# Keypad_Controller.net
KiCad netlist of a schematic drawn in Altium Designer
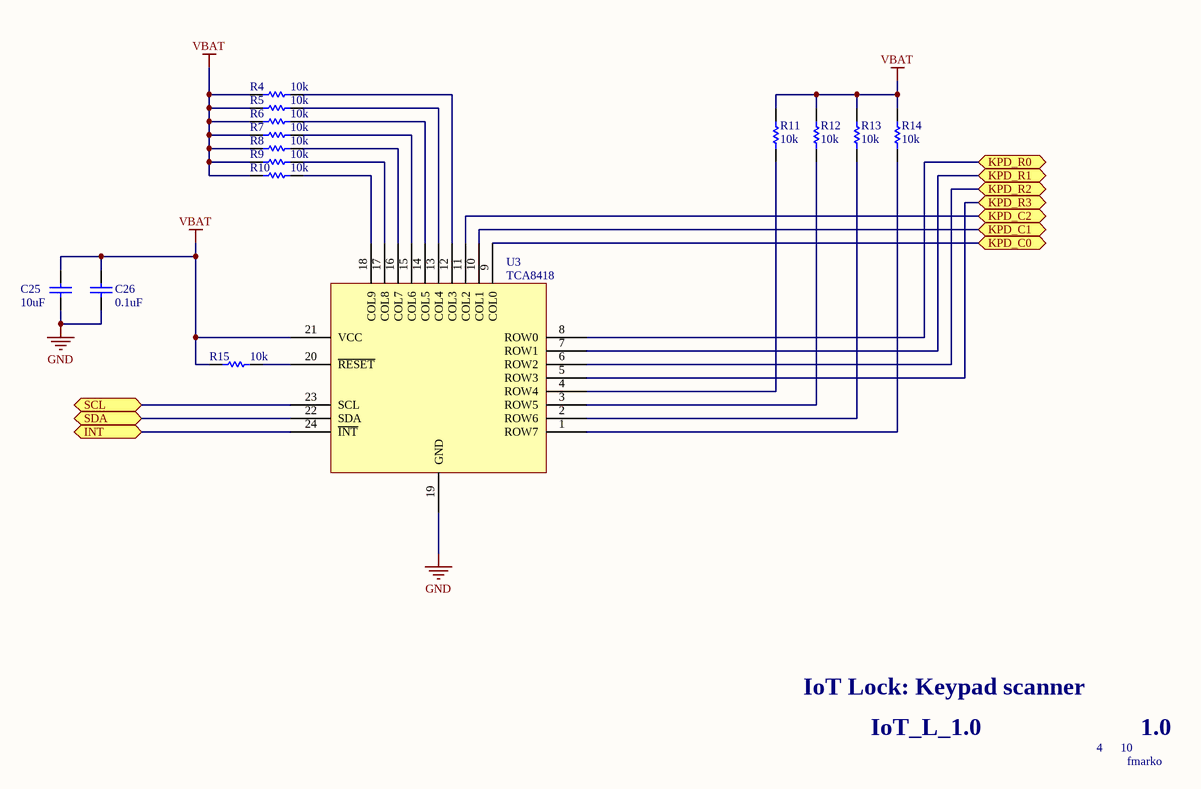
[diagram p0: Keypad Controller.SchDoc]

(export (version "E")
  (design (tool "Eeschema 10.0.6"))
  (components
    (comp (ref "C25")
      (value "10uF")
      (footprint "1608[0603]")
      (description "Capacitor")
      (fields (field (name "Comment") "GRM1555C1HR50BA01D") (field (name "PUBLISHER") "Altium Limited"))
      (libsource (lib "Miscellaneous Devices") (part "Cap"))
    )
    (comp (ref "C26")
      (value "0.1uF")
      (footprint "0402")
      (description "Capacitor")
      (fields (field (name "Comment") "GRM1555C1HR50BA01D") (field (name "PUBLISHER") "Altium Limited"))
      (libsource (lib "Miscellaneous Devices") (part "Cap"))
    )
    (comp (ref "R4")
      (value "10k")
      (footprint "0402")
      (description "Semiconductor Resistor")
      (fields (field (name "Comment") "Res Semi") (field (name "PUBLISHER") "Altium Limited"))
      (libsource (lib "Miscellaneous Devices") (part "Res Semi"))
    )
    (comp (ref "R5")
      (value "10k")
      (footprint "0402")
      (description "Semiconductor Resistor")
      (fields (field (name "Comment") "Res Semi") (field (name "PUBLISHER") "Altium Limited"))
      (libsource (lib "Miscellaneous Devices") (part "Res Semi"))
    )
    (comp (ref "R6")
      (value "10k")
      (footprint "0402")
      (description "Semiconductor Resistor")
      (fields (field (name "Comment") "Res Semi") (field (name "PUBLISHER") "Altium Limited"))
      (libsource (lib "Miscellaneous Devices") (part "Res Semi"))
    )
    (comp (ref "R7")
      (value "10k")
      (footprint "0402")
      (description "Semiconductor Resistor")
      (fields (field (name "Comment") "Res Semi") (field (name "PUBLISHER") "Altium Limited"))
      (libsource (lib "Miscellaneous Devices") (part "Res Semi"))
    )
    (comp (ref "R8")
      (value "10k")
      (footprint "0402")
      (description "Semiconductor Resistor")
      (fields (field (name "Comment") "Res Semi") (field (name "PUBLISHER") "Altium Limited"))
      (libsource (lib "Miscellaneous Devices") (part "Res Semi"))
    )
    (comp (ref "R9")
      (value "10k")
      (footprint "0402")
      (description "Semiconductor Resistor")
      (fields (field (name "Comment") "Res Semi") (field (name "PUBLISHER") "Altium Limited"))
      (libsource (lib "Miscellaneous Devices") (part "Res Semi"))
    )
    (comp (ref "R10")
      (value "10k")
      (footprint "0402")
      (description "Semiconductor Resistor")
      (fields (field (name "Comment") "Res Semi") (field (name "PUBLISHER") "Altium Limited"))
      (libsource (lib "Miscellaneous Devices") (part "Res Semi"))
    )
    (comp (ref "R11")
      (value "10k")
      (footprint "0402")
      (description "Semiconductor Resistor")
      (fields (field (name "Comment") "Res Semi") (field (name "PUBLISHER") "Altium Limited"))
      (libsource (lib "Miscellaneous Devices") (part "Res Semi"))
    )
    (comp (ref "R12")
      (value "10k")
      (footprint "0402")
      (description "Semiconductor Resistor")
      (fields (field (name "Comment") "Res Semi") (field (name "PUBLISHER") "Altium Limited"))
      (libsource (lib "Miscellaneous Devices") (part "Res Semi"))
    )
    (comp (ref "R13")
      (value "10k")
      (footprint "0402")
      (description "Semiconductor Resistor")
      (fields (field (name "Comment") "Res Semi") (field (name "PUBLISHER") "Altium Limited"))
      (libsource (lib "Miscellaneous Devices") (part "Res Semi"))
    )
    (comp (ref "R14")
      (value "10k")
      (footprint "0402")
      (description "Semiconductor Resistor")
      (fields (field (name "Comment") "Res Semi") (field (name "PUBLISHER") "Altium Limited"))
      (libsource (lib "Miscellaneous Devices") (part "Res Semi"))
    )
    (comp (ref "R15")
      (value "10k")
      (footprint "0402")
      (description "Semiconductor Resistor")
      (fields (field (name "Comment") "Res Semi") (field (name "PUBLISHER") "Altium Limited"))
      (libsource (lib "Miscellaneous Devices") (part "Res Semi"))
    )
    (comp (ref "U3")
      (value "TCA8418")
      (footprint "PQFN50P400X400X80_HS-25N")
      (description "I2C keyboard controller, TI")
      (libsource (lib "TCA8418") (part "TCA8418"))
    )
  )
  (nets
    (net (code "1") (name "/INT") (class "Default")
      (node (ref "U3") (pin "24") (pinfunction "~{INT}_24") (pintype "passive"))
    )
    (net (code "2") (name "/KPD_C0") (class "Default")
      (node (ref "U3") (pin "9") (pinfunction "COL0_9") (pintype "passive"))
    )
    (net (code "3") (name "/KPD_C1") (class "Default")
      (node (ref "U3") (pin "10") (pinfunction "COL1_10") (pintype "passive"))
    )
    (net (code "4") (name "/KPD_C2") (class "Default")
      (node (ref "U3") (pin "11") (pinfunction "COL2_11") (pintype "passive"))
    )
    (net (code "5") (name "/KPD_R0") (class "Default")
      (node (ref "U3") (pin "8") (pinfunction "ROW0_8") (pintype "passive"))
    )
    (net (code "6") (name "/KPD_R1") (class "Default")
      (node (ref "U3") (pin "7") (pinfunction "ROW1_7") (pintype "passive"))
    )
    (net (code "7") (name "/KPD_R2") (class "Default")
      (node (ref "U3") (pin "6") (pinfunction "ROW2_6") (pintype "passive"))
    )
    (net (code "8") (name "/KPD_R3") (class "Default")
      (node (ref "U3") (pin "5") (pinfunction "ROW3_5") (pintype "passive"))
    )
    (net (code "9") (name "/SCL") (class "Default")
      (node (ref "U3") (pin "23") (pinfunction "SCL_23") (pintype "passive"))
    )
    (net (code "10") (name "/SDA") (class "Default")
      (node (ref "U3") (pin "22") (pinfunction "SDA_22") (pintype "passive"))
    )
    (net (code "11") (name "GND") (class "Default")
      (node (ref "C25") (pin "1") (pinfunction "1_1") (pintype "passive"))
      (node (ref "C26") (pin "1") (pinfunction "1_1") (pintype "passive"))
      (node (ref "U3") (pin "19") (pinfunction "GND_19") (pintype "passive"))
    )
    (net (code "12") (name "Net-(U3-COL3)") (class "Default")
      (node (ref "R4") (pin "2") (pinfunction "2_2") (pintype "passive"))
      (node (ref "U3") (pin "12") (pinfunction "COL3_12") (pintype "passive"))
    )
    (net (code "13") (name "Net-(U3-COL4)") (class "Default")
      (node (ref "R5") (pin "2") (pinfunction "2_2") (pintype "passive"))
      (node (ref "U3") (pin "13") (pinfunction "COL4_13") (pintype "passive"))
    )
    (net (code "14") (name "Net-(U3-COL5)") (class "Default")
      (node (ref "R6") (pin "2") (pinfunction "2_2") (pintype "passive"))
      (node (ref "U3") (pin "14") (pinfunction "COL5_14") (pintype "passive"))
    )
    (net (code "15") (name "Net-(U3-COL6)") (class "Default")
      (node (ref "R7") (pin "2") (pinfunction "2_2") (pintype "passive"))
      (node (ref "U3") (pin "15") (pinfunction "COL6_15") (pintype "passive"))
    )
    (net (code "16") (name "Net-(U3-COL7)") (class "Default")
      (node (ref "R8") (pin "2") (pinfunction "2_2") (pintype "passive"))
      (node (ref "U3") (pin "16") (pinfunction "COL7_16") (pintype "passive"))
    )
    (net (code "17") (name "Net-(U3-COL8)") (class "Default")
      (node (ref "R9") (pin "2") (pinfunction "2_2") (pintype "passive"))
      (node (ref "U3") (pin "17") (pinfunction "COL8_17") (pintype "passive"))
    )
    (net (code "18") (name "Net-(U3-COL9)") (class "Default")
      (node (ref "R10") (pin "2") (pinfunction "2_2") (pintype "passive"))
      (node (ref "U3") (pin "18") (pinfunction "COL9_18") (pintype "passive"))
    )
    (net (code "19") (name "Net-(U3-ROW4)") (class "Default")
      (node (ref "R11") (pin "1") (pinfunction "1_1") (pintype "passive"))
      (node (ref "U3") (pin "4") (pinfunction "ROW4_4") (pintype "passive"))
    )
    (net (code "20") (name "Net-(U3-ROW5)") (class "Default")
      (node (ref "R12") (pin "1") (pinfunction "1_1") (pintype "passive"))
      (node (ref "U3") (pin "3") (pinfunction "ROW5_3") (pintype "passive"))
    )
    (net (code "21") (name "Net-(U3-ROW6)") (class "Default")
      (node (ref "R13") (pin "1") (pinfunction "1_1") (pintype "passive"))
      (node (ref "U3") (pin "2") (pinfunction "ROW6_2") (pintype "passive"))
    )
    (net (code "22") (name "Net-(U3-ROW7)") (class "Default")
      (node (ref "R14") (pin "1") (pinfunction "1_1") (pintype "passive"))
      (node (ref "U3") (pin "1") (pinfunction "ROW7_1") (pintype "passive"))
    )
    (net (code "23") (name "Net-(U3-~{RESET})") (class "Default")
      (node (ref "R15") (pin "2") (pinfunction "2_2") (pintype "passive"))
      (node (ref "U3") (pin "20") (pinfunction "~{RESET}_20") (pintype "passive"))
    )
    (net (code "24") (name "VBAT") (class "Default")
      (node (ref "C25") (pin "2") (pinfunction "2_2") (pintype "passive"))
      (node (ref "C26") (pin "2") (pinfunction "2_2") (pintype "passive"))
      (node (ref "R10") (pin "1") (pinfunction "1_1") (pintype "passive"))
      (node (ref "R11") (pin "2") (pinfunction "2_2") (pintype "passive"))
      (node (ref "R12") (pin "2") (pinfunction "2_2") (pintype "passive"))
      (node (ref "R13") (pin "2") (pinfunction "2_2") (pintype "passive"))
      (node (ref "R14") (pin "2") (pinfunction "2_2") (pintype "passive"))
      (node (ref "R15") (pin "1") (pinfunction "1_1") (pintype "passive"))
      (node (ref "R4") (pin "1") (pinfunction "1_1") (pintype "passive"))
      (node (ref "R5") (pin "1") (pinfunction "1_1") (pintype "passive"))
      (node (ref "R6") (pin "1") (pinfunction "1_1") (pintype "passive"))
      (node (ref "R7") (pin "1") (pinfunction "1_1") (pintype "passive"))
      (node (ref "R8") (pin "1") (pinfunction "1_1") (pintype "passive"))
      (node (ref "R9") (pin "1") (pinfunction "1_1") (pintype "passive"))
      (node (ref "U3") (pin "21") (pinfunction "VCC_21") (pintype "passive"))
    )
  )
)
